# EncoderPCB_V1_3.net
KiCad netlist of a schematic drawn in EAGLE
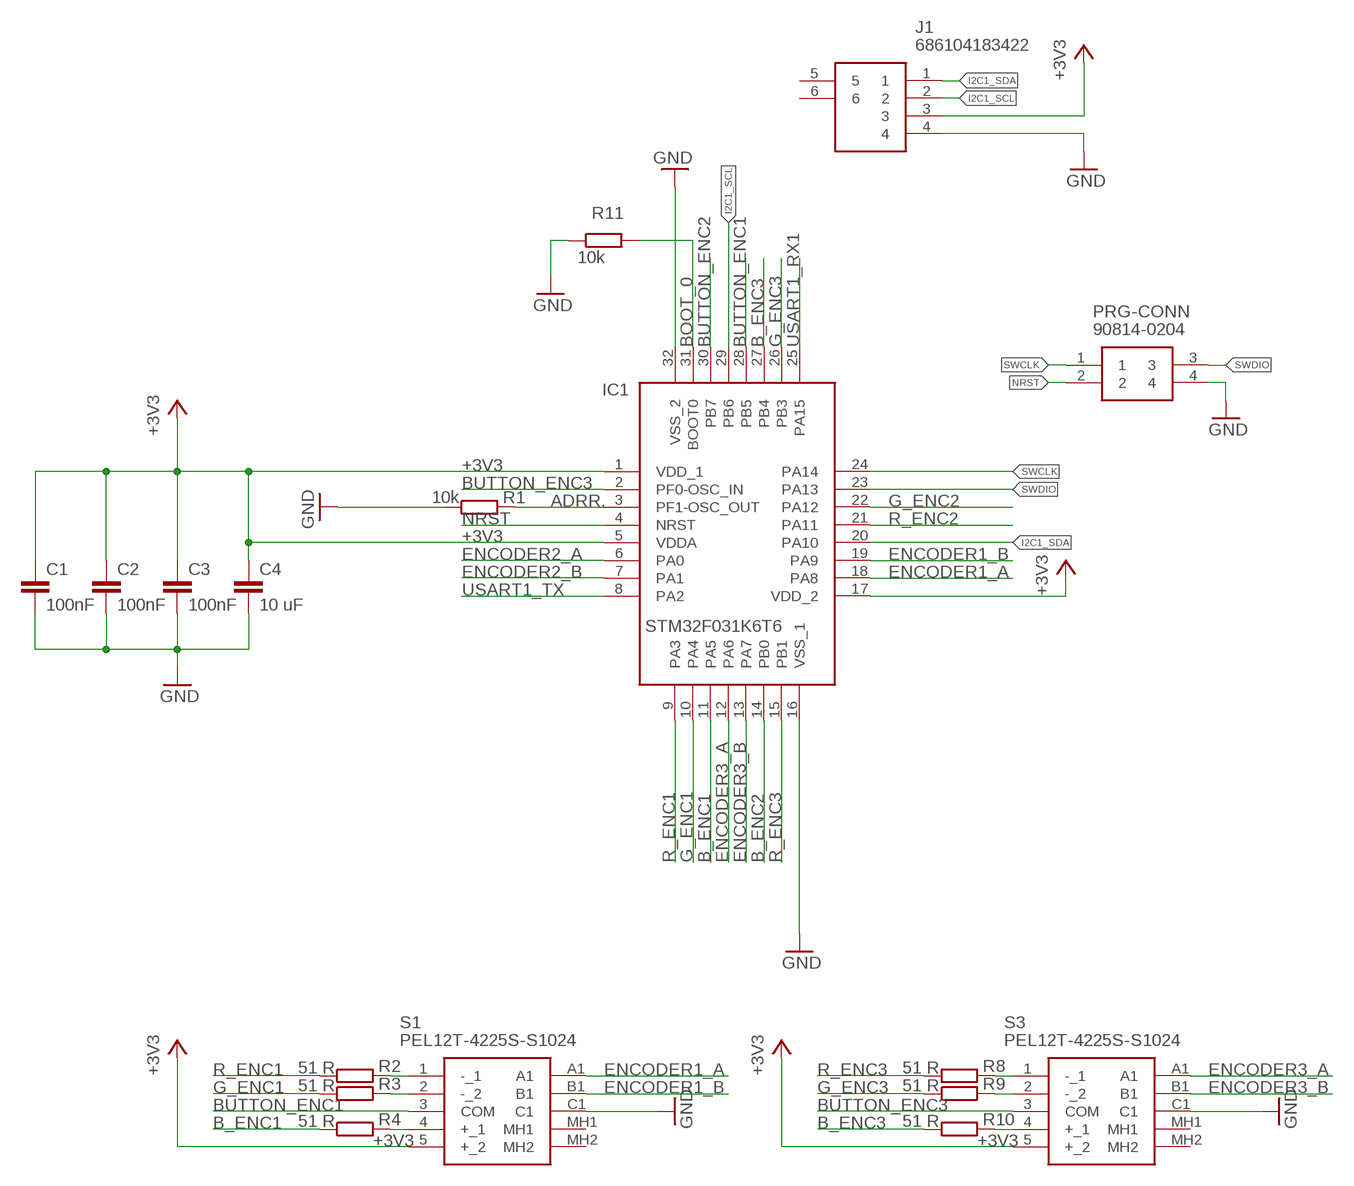
[diagram p0: schematic, sheet 1]

(export (version "E")
  (design (tool "Eeschema 10.0.6"))
  (components
    (comp (ref "C1")
      (value "100nF")
      (footprint "eagle-import:C0603")
      (libsource (lib "eagle-import") (part "CAPACITOR{dblquote}"))
    )
    (comp (ref "C2")
      (value "100nF")
      (footprint "eagle-import:C0603")
      (libsource (lib "eagle-import") (part "CAPACITOR{dblquote}"))
    )
    (comp (ref "C3")
      (value "100nF")
      (footprint "eagle-import:C0603")
      (libsource (lib "eagle-import") (part "CAPACITOR{dblquote}"))
    )
    (comp (ref "C4")
      (value "10 uF")
      (footprint "eagle-import:C1206")
      (libsource (lib "eagle-import") (part "CAPACITOR_1206"))
    )
    (comp (ref "IC1")
      (value "STM32F031K6T6")
      (footprint "eagle-import:QFP80P900X900X160-32N")
      (fields (field (name "MOUSER_PART_NUMBER") "511-STM32F031K6T6"))
      (libsource (lib "eagle-import") (part "STM32F031K6T6"))
    )
    (comp (ref "J1")
      (value "686104183422")
      (footprint "eagle-import:686104183422")
      (fields (field (name "MOUSER_PART_NUMBER") "710-686104183422"))
      (libsource (lib "eagle-import") (part "686104183422"))
    )
    (comp (ref "PRG-CONN")
      (value "90814-0204")
      (footprint "eagle-import:MOLEX_90814-0204")
      (fields (field (name "MOUSER_PART_NUMBER") "538-90814-0204"))
      (libsource (lib "eagle-import") (part "90814-0204"))
    )
    (comp (ref "R1")
      (value "10k")
      (footprint "eagle-import:R0603")
      (libsource (lib "eagle-import") (part "RESISTOR_0603"))
    )
    (comp (ref "R2")
      (value "51 R")
      (footprint "eagle-import:R0603")
      (libsource (lib "eagle-import") (part "RESISTOR_0603"))
    )
    (comp (ref "R3")
      (value "51 R")
      (footprint "eagle-import:R0603")
      (libsource (lib "eagle-import") (part "RESISTOR_0603"))
    )
    (comp (ref "R4")
      (value "51 R")
      (footprint "eagle-import:R0603")
      (libsource (lib "eagle-import") (part "RESISTOR_0603"))
    )
    (comp (ref "R8")
      (value "51 R")
      (footprint "eagle-import:R0603")
      (libsource (lib "eagle-import") (part "RESISTOR_0603"))
    )
    (comp (ref "R9")
      (value "51 R")
      (footprint "eagle-import:R0603")
      (libsource (lib "eagle-import") (part "RESISTOR_0603"))
    )
    (comp (ref "R10")
      (value "51 R")
      (footprint "eagle-import:R0603")
      (libsource (lib "eagle-import") (part "RESISTOR_0603"))
    )
    (comp (ref "R11")
      (value "10k")
      (footprint "eagle-import:R0603")
      (libsource (lib "eagle-import") (part "RESISTOR_0603"))
    )
    (comp (ref "S1")
      (value "PEL12T-4225S-S1024")
      (footprint "eagle-import:PEL12T4225SS1024")
      (fields (field (name "MOUSER_PART_NUMBER") "652-PEL12T4225SS1024"))
      (libsource (lib "eagle-import") (part "PEL12T-4225S-S1024"))
    )
    (comp (ref "S3")
      (value "PEL12T-4225S-S1024")
      (footprint "eagle-import:PEL12T4225SS1024")
      (fields (field (name "MOUSER_PART_NUMBER") "652-PEL12T4225SS1024"))
      (libsource (lib "eagle-import") (part "PEL12T-4225S-S1024"))
    )
  )
  (nets
    (net (code "1") (name "+3V3") (class "Default")
      (node (ref "C1") (pin "1") (pinfunction "1_1") (pintype "passive"))
      (node (ref "C2") (pin "1") (pinfunction "1_1") (pintype "passive"))
      (node (ref "C3") (pin "1") (pinfunction "1_1") (pintype "passive"))
      (node (ref "C4") (pin "1") (pinfunction "1_1") (pintype "passive"))
      (node (ref "IC1") (pin "1") (pinfunction "VDD_1_1") (pintype "bidirectional"))
      (node (ref "IC1") (pin "17") (pinfunction "VDD_2_17") (pintype "bidirectional"))
      (node (ref "IC1") (pin "5") (pinfunction "VDDA_5") (pintype "bidirectional"))
      (node (ref "J1") (pin "3") (pinfunction "3_3") (pintype "bidirectional"))
      (node (ref "S1") (pin "5") (pinfunction "+_2_5") (pintype "bidirectional"))
      (node (ref "S3") (pin "5") (pinfunction "+_2_5") (pintype "bidirectional"))
    )
    (net (code "2") (name "/ADRR.") (class "Default")
      (node (ref "IC1") (pin "3") (pinfunction "PF1-OSC_OUT_3") (pintype "bidirectional"))
      (node (ref "R1") (pin "2") (pinfunction "2_2") (pintype "passive"))
    )
    (net (code "3") (name "/BOOT_0") (class "Default")
      (node (ref "IC1") (pin "31") (pinfunction "BOOT0_31") (pintype "bidirectional"))
      (node (ref "R11") (pin "2") (pinfunction "2_2") (pintype "passive"))
    )
    (net (code "4") (name "/BUTTON_ENC1") (class "Default")
      (node (ref "IC1") (pin "28") (pinfunction "PB5_28") (pintype "bidirectional"))
      (node (ref "S1") (pin "3") (pinfunction "COM_3") (pintype "bidirectional"))
    )
    (net (code "5") (name "/BUTTON_ENC2") (class "Default")
      (node (ref "IC1") (pin "30") (pinfunction "PB7_30") (pintype "bidirectional"))
    )
    (net (code "6") (name "/BUTTON_ENC3") (class "Default")
      (node (ref "IC1") (pin "2") (pinfunction "PF0-OSC_IN_2") (pintype "bidirectional"))
      (node (ref "S3") (pin "3") (pinfunction "COM_3") (pintype "bidirectional"))
    )
    (net (code "7") (name "/B_ENC1") (class "Default")
      (node (ref "IC1") (pin "11") (pinfunction "PA5_11") (pintype "bidirectional"))
      (node (ref "R4") (pin "1") (pinfunction "1_1") (pintype "passive"))
    )
    (net (code "8") (name "/B_ENC2") (class "Default")
      (node (ref "IC1") (pin "14") (pinfunction "PB0_14") (pintype "bidirectional"))
    )
    (net (code "9") (name "/B_ENC3") (class "Default")
      (node (ref "IC1") (pin "27") (pinfunction "PB4_27") (pintype "bidirectional"))
      (node (ref "R10") (pin "1") (pinfunction "1_1") (pintype "passive"))
    )
    (net (code "10") (name "/ENCODER1_A") (class "Default")
      (node (ref "IC1") (pin "18") (pinfunction "PA8_18") (pintype "bidirectional"))
      (node (ref "S1") (pin "A1") (pinfunction "A1_A1") (pintype "bidirectional"))
    )
    (net (code "11") (name "/ENCODER1_B") (class "Default")
      (node (ref "IC1") (pin "19") (pinfunction "PA9_19") (pintype "bidirectional"))
      (node (ref "S1") (pin "B1") (pinfunction "B1_B1") (pintype "bidirectional"))
    )
    (net (code "12") (name "/ENCODER2_A") (class "Default")
      (node (ref "IC1") (pin "6") (pinfunction "PA0_6") (pintype "bidirectional"))
    )
    (net (code "13") (name "/ENCODER2_B") (class "Default")
      (node (ref "IC1") (pin "7") (pinfunction "PA1_7") (pintype "bidirectional"))
    )
    (net (code "14") (name "/ENCODER3_A") (class "Default")
      (node (ref "IC1") (pin "12") (pinfunction "PA6_12") (pintype "bidirectional"))
      (node (ref "S3") (pin "A1") (pinfunction "A1_A1") (pintype "bidirectional"))
    )
    (net (code "15") (name "/ENCODER3_B") (class "Default")
      (node (ref "IC1") (pin "13") (pinfunction "PA7_13") (pintype "bidirectional"))
      (node (ref "S3") (pin "B1") (pinfunction "B1_B1") (pintype "bidirectional"))
    )
    (net (code "16") (name "/G_ENC1") (class "Default")
      (node (ref "IC1") (pin "10") (pinfunction "PA4_10") (pintype "bidirectional"))
      (node (ref "R3") (pin "1") (pinfunction "1_1") (pintype "passive"))
    )
    (net (code "17") (name "/G_ENC2") (class "Default")
      (node (ref "IC1") (pin "22") (pinfunction "PA12_22") (pintype "bidirectional"))
    )
    (net (code "18") (name "/G_ENC3") (class "Default")
      (node (ref "IC1") (pin "26") (pinfunction "PB3_26") (pintype "bidirectional"))
      (node (ref "R9") (pin "1") (pinfunction "1_1") (pintype "passive"))
    )
    (net (code "19") (name "/R_ENC1") (class "Default")
      (node (ref "IC1") (pin "9") (pinfunction "PA3_9") (pintype "bidirectional"))
      (node (ref "R2") (pin "1") (pinfunction "1_1") (pintype "passive"))
    )
    (net (code "20") (name "/R_ENC2") (class "Default")
      (node (ref "IC1") (pin "21") (pinfunction "PA11_21") (pintype "bidirectional"))
    )
    (net (code "21") (name "/R_ENC3") (class "Default")
      (node (ref "IC1") (pin "15") (pinfunction "PB1_15") (pintype "bidirectional"))
      (node (ref "R8") (pin "1") (pinfunction "1_1") (pintype "passive"))
    )
    (net (code "22") (name "/USART1_RX1") (class "Default")
      (node (ref "IC1") (pin "25") (pinfunction "PA15_25") (pintype "bidirectional"))
    )
    (net (code "23") (name "/USART1_TX") (class "Default")
      (node (ref "IC1") (pin "8") (pinfunction "PA2_8") (pintype "bidirectional"))
    )
    (net (code "24") (name "GND") (class "Default")
      (node (ref "C1") (pin "2") (pinfunction "2_2") (pintype "passive"))
      (node (ref "C2") (pin "2") (pinfunction "2_2") (pintype "passive"))
      (node (ref "C3") (pin "2") (pinfunction "2_2") (pintype "passive"))
      (node (ref "C4") (pin "2") (pinfunction "2_2") (pintype "passive"))
      (node (ref "IC1") (pin "16") (pinfunction "VSS_1_16") (pintype "bidirectional"))
      (node (ref "IC1") (pin "32") (pinfunction "VSS_2_32") (pintype "bidirectional"))
      (node (ref "J1") (pin "4") (pinfunction "4_4") (pintype "bidirectional"))
      (node (ref "PRG-CONN") (pin "4") (pinfunction "4_4") (pintype "bidirectional"))
      (node (ref "R1") (pin "1") (pinfunction "1_1") (pintype "passive"))
      (node (ref "R11") (pin "1") (pinfunction "1_1") (pintype "passive"))
      (node (ref "S1") (pin "C1") (pinfunction "C1_C1") (pintype "bidirectional"))
      (node (ref "S3") (pin "C1") (pinfunction "C1_C1") (pintype "bidirectional"))
    )
    (net (code "25") (name "I2C1_SCL") (class "Default")
      (node (ref "IC1") (pin "29") (pinfunction "PB6_29") (pintype "bidirectional"))
      (node (ref "J1") (pin "2") (pinfunction "2_2") (pintype "bidirectional"))
    )
    (net (code "26") (name "I2C1_SDA") (class "Default")
      (node (ref "IC1") (pin "20") (pinfunction "PA10_20") (pintype "bidirectional"))
      (node (ref "J1") (pin "1") (pinfunction "1_1") (pintype "bidirectional"))
    )
    (net (code "27") (name "NRST") (class "Default")
      (node (ref "IC1") (pin "4") (pinfunction "NRST_4") (pintype "bidirectional"))
      (node (ref "PRG-CONN") (pin "2") (pinfunction "2_2") (pintype "bidirectional"))
    )
    (net (code "28") (name "Net-(S1-+_1)") (class "Default")
      (node (ref "R4") (pin "2") (pinfunction "2_2") (pintype "passive"))
      (node (ref "S1") (pin "4") (pinfunction "+_1_4") (pintype "bidirectional"))
    )
    (net (code "29") (name "Net-(S1--_1)") (class "Default")
      (node (ref "R2") (pin "2") (pinfunction "2_2") (pintype "passive"))
      (node (ref "S1") (pin "1") (pinfunction "-_1_1") (pintype "bidirectional"))
    )
    (net (code "30") (name "Net-(S1--_2)") (class "Default")
      (node (ref "R3") (pin "2") (pinfunction "2_2") (pintype "passive"))
      (node (ref "S1") (pin "2") (pinfunction "-_2_2") (pintype "bidirectional"))
    )
    (net (code "31") (name "Net-(S3-+_1)") (class "Default")
      (node (ref "R10") (pin "2") (pinfunction "2_2") (pintype "passive"))
      (node (ref "S3") (pin "4") (pinfunction "+_1_4") (pintype "bidirectional"))
    )
    (net (code "32") (name "Net-(S3--_1)") (class "Default")
      (node (ref "R8") (pin "2") (pinfunction "2_2") (pintype "passive"))
      (node (ref "S3") (pin "1") (pinfunction "-_1_1") (pintype "bidirectional"))
    )
    (net (code "33") (name "Net-(S3--_2)") (class "Default")
      (node (ref "R9") (pin "2") (pinfunction "2_2") (pintype "passive"))
      (node (ref "S3") (pin "2") (pinfunction "-_2_2") (pintype "bidirectional"))
    )
    (net (code "34") (name "SWCLK") (class "Default")
      (node (ref "IC1") (pin "24") (pinfunction "PA14_24") (pintype "bidirectional"))
      (node (ref "PRG-CONN") (pin "1") (pinfunction "1_1") (pintype "bidirectional"))
    )
    (net (code "35") (name "SWDIO") (class "Default")
      (node (ref "IC1") (pin "23") (pinfunction "PA13_23") (pintype "bidirectional"))
      (node (ref "PRG-CONN") (pin "3") (pinfunction "3_3") (pintype "bidirectional"))
    )
    (net (code "36") (name "unconnected-(J1-Pad5)") (class "Default")
      (node (ref "J1") (pin "5") (pinfunction "5_5") (pintype "bidirectional"))
    )
    (net (code "37") (name "unconnected-(J1-Pad6)") (class "Default")
      (node (ref "J1") (pin "6") (pinfunction "6_6") (pintype "bidirectional"))
    )
    (net (code "38") (name "unconnected-(S1-PadMH1)") (class "Default")
      (node (ref "S1") (pin "MH1") (pinfunction "MH1_MH1") (pintype "bidirectional"))
    )
    (net (code "39") (name "unconnected-(S1-PadMH2)") (class "Default")
      (node (ref "S1") (pin "MH2") (pinfunction "MH2_MH2") (pintype "bidirectional"))
    )
    (net (code "40") (name "unconnected-(S3-PadMH1)") (class "Default")
      (node (ref "S3") (pin "MH1") (pinfunction "MH1_MH1") (pintype "bidirectional"))
    )
    (net (code "41") (name "unconnected-(S3-PadMH2)") (class "Default")
      (node (ref "S3") (pin "MH2") (pinfunction "MH2_MH2") (pintype "bidirectional"))
    )
  )
)
